# ADS1220RTD_BREWNO_V2.net
KiCad netlist of a schematic drawn in EAGLE
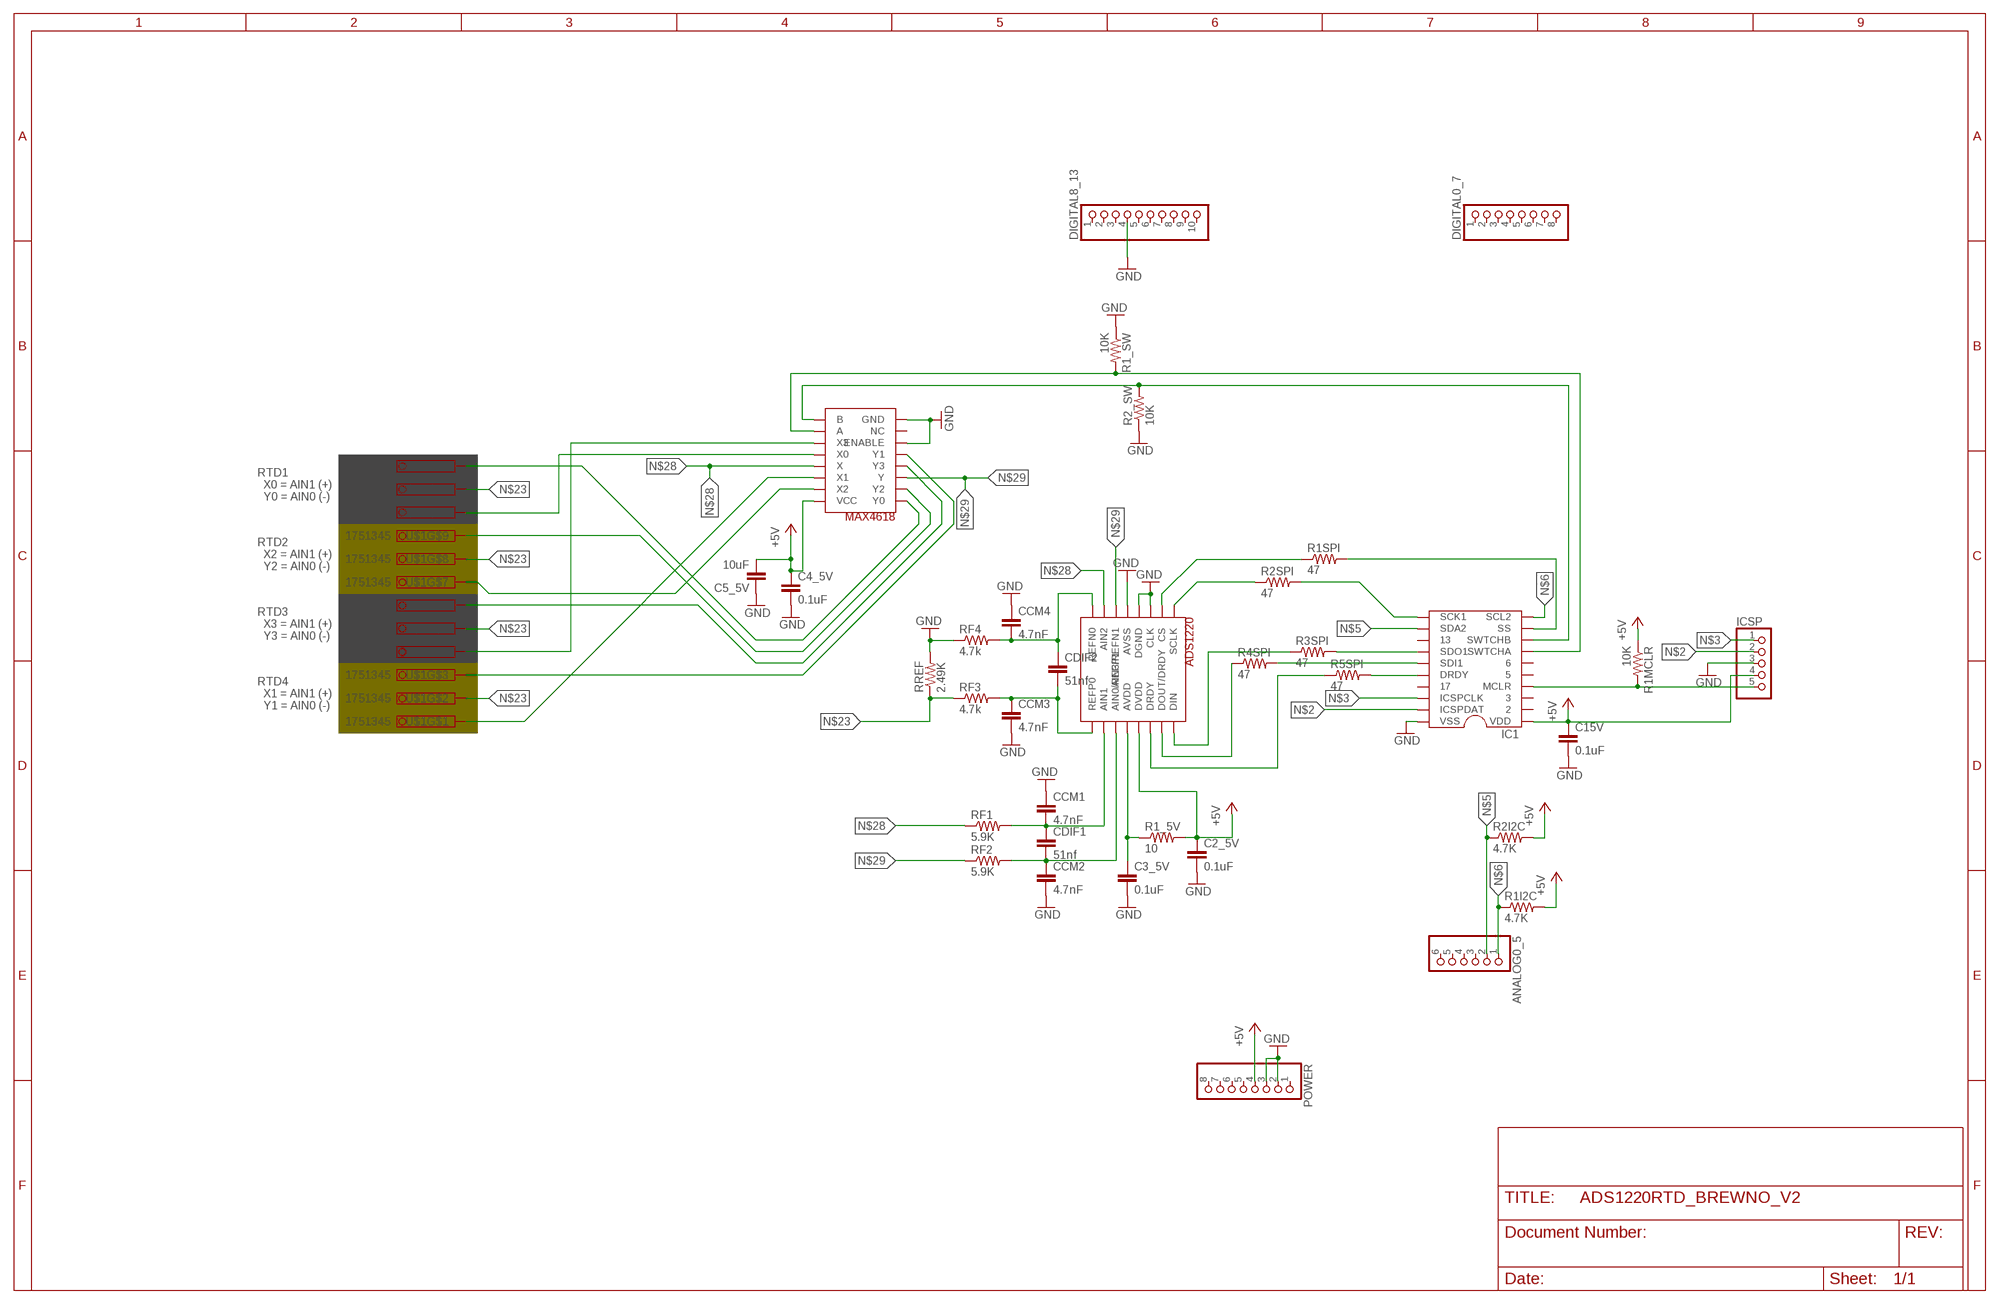
[diagram p0: schematic, sheet 1]

(export (version "E")
  (design (tool "Eeschema 10.0.6"))
  (components
    (comp (ref "ADS1220")
      (value "ADS1220")
      (footprint "eagle-import:TSSOP16")
      (libsource (lib "eagle-import") (part "ADS1220"))
    )
    (comp (ref "ANALOG0_5")
      (value "PINHD-1X6")
      (footprint "eagle-import:1X06")
      (libsource (lib "eagle-import") (part "PINHD-1X6"))
    )
    (comp (ref "C2_5V")
      (value "0.1uF")
      (footprint "eagle-import:C0603")
      (libsource (lib "eagle-import") (part "C-EUC0603"))
    )
    (comp (ref "C3_5V")
      (value "0.1uF")
      (footprint "eagle-import:C0603")
      (libsource (lib "eagle-import") (part "C-EUC0603"))
    )
    (comp (ref "C4_5V")
      (value "0.1uF")
      (footprint "eagle-import:C0603")
      (libsource (lib "eagle-import") (part "C-EUC0603"))
    )
    (comp (ref "C5_5V")
      (value "10uF")
      (footprint "eagle-import:C0603")
      (libsource (lib "eagle-import") (part "C-EUC0603"))
    )
    (comp (ref "C15V")
      (value "0.1uF")
      (footprint "eagle-import:C0603")
      (libsource (lib "eagle-import") (part "C-EUC0603"))
    )
    (comp (ref "CCM1")
      (value "4.7nF")
      (footprint "eagle-import:C0603")
      (libsource (lib "eagle-import") (part "C-EUC0603"))
    )
    (comp (ref "CCM2")
      (value "4.7nF")
      (footprint "eagle-import:C0603")
      (libsource (lib "eagle-import") (part "C-EUC0603"))
    )
    (comp (ref "CCM3")
      (value "4.7nF")
      (footprint "eagle-import:C0603")
      (libsource (lib "eagle-import") (part "C-EUC0603"))
    )
    (comp (ref "CCM4")
      (value "4.7nF")
      (footprint "eagle-import:C0603")
      (libsource (lib "eagle-import") (part "C-EUC0603"))
    )
    (comp (ref "CDIF1")
      (value "51nf")
      (footprint "eagle-import:C1206")
      (libsource (lib "eagle-import") (part "C-EUC1206"))
    )
    (comp (ref "CDIF2")
      (value "51nf")
      (footprint "eagle-import:C1206")
      (libsource (lib "eagle-import") (part "C-EUC1206"))
    )
    (comp (ref "DIGITAL0_7")
      (value "PINHD-1X8")
      (footprint "eagle-import:1X08")
      (libsource (lib "eagle-import") (part "PINHD-1X8"))
    )
    (comp (ref "DIGITAL8_13")
      (value "PINHD-1X10")
      (footprint "eagle-import:1X10")
      (libsource (lib "eagle-import") (part "PINHD-1X10"))
    )
    (comp (ref "IC1")
      (value "DIL20")
      (footprint "eagle-import:DIL20")
      (libsource (lib "eagle-import") (part "DIL20"))
    )
    (comp (ref "ICSP")
      (value "PINHD-1X5")
      (footprint "eagle-import:1X05")
      (libsource (lib "eagle-import") (part "PINHD-1X5"))
    )
    (comp (ref "MAX4618")
      (value "MAX4618CPE")
      (footprint "eagle-import:SO16")
      (libsource (lib "eagle-import") (part "MAX4618CPE"))
    )
    (comp (ref "POWER")
      (value "PINHD-1X8")
      (footprint "eagle-import:1X08")
      (libsource (lib "eagle-import") (part "PINHD-1X8"))
    )
    (comp (ref "R1I2C")
      (value "4.7K")
      (footprint "eagle-import:R0603")
      (libsource (lib "eagle-import") (part "R-US_R0603"))
    )
    (comp (ref "R1MCLR")
      (value "10K")
      (footprint "eagle-import:R0603")
      (libsource (lib "eagle-import") (part "R-US_R0603"))
    )
    (comp (ref "R1SPI")
      (value "47")
      (footprint "eagle-import:R0603")
      (libsource (lib "eagle-import") (part "R-US_R0603"))
    )
    (comp (ref "R1_5V")
      (value "10")
      (footprint "eagle-import:R0603")
      (libsource (lib "eagle-import") (part "R-US_R0603"))
    )
    (comp (ref "R1_SW")
      (value "10K")
      (footprint "eagle-import:R0603")
      (libsource (lib "eagle-import") (part "R-US_R0603"))
    )
    (comp (ref "R2I2C")
      (value "4.7K")
      (footprint "eagle-import:R0603")
      (libsource (lib "eagle-import") (part "R-US_R0603"))
    )
    (comp (ref "R2SPI")
      (value "47")
      (footprint "eagle-import:R0603")
      (libsource (lib "eagle-import") (part "R-US_R0603"))
    )
    (comp (ref "R2_SW")
      (value "10K")
      (footprint "eagle-import:R0603")
      (libsource (lib "eagle-import") (part "R-US_R0603"))
    )
    (comp (ref "R3SPI")
      (value "47")
      (footprint "eagle-import:R0603")
      (libsource (lib "eagle-import") (part "R-US_R0603"))
    )
    (comp (ref "R4SPI")
      (value "47")
      (footprint "eagle-import:R0603")
      (libsource (lib "eagle-import") (part "R-US_R0603"))
    )
    (comp (ref "R5SPI")
      (value "47")
      (footprint "eagle-import:R0603")
      (libsource (lib "eagle-import") (part "R-US_R0603"))
    )
    (comp (ref "RF1")
      (value "5.9K")
      (footprint "eagle-import:R0603")
      (libsource (lib "eagle-import") (part "R-US_R0603"))
    )
    (comp (ref "RF2")
      (value "5.9K")
      (footprint "eagle-import:R0603")
      (libsource (lib "eagle-import") (part "R-US_R0603"))
    )
    (comp (ref "RF3")
      (value "4.7k")
      (footprint "eagle-import:R0603")
      (libsource (lib "eagle-import") (part "R-US_R0603"))
    )
    (comp (ref "RF4")
      (value "4.7k")
      (footprint "eagle-import:R0603")
      (libsource (lib "eagle-import") (part "R-US_R0603"))
    )
    (comp (ref "RREF")
      (value "2.49K")
      (footprint "eagle-import:R0603")
      (libsource (lib "eagle-import") (part "R-US_R0603"))
    )
    (comp (ref "U$1")
      (value "1751345")
      (footprint "eagle-import:1751345")
      (libsource (lib "eagle-import") (part "1751345"))
    )
  )
  (nets
    (net (code "1") (name "+5V") (class "Default")
      (node (ref "ADS1220") (pin "13") (pinfunction "DVDD_13") (pintype "bidirectional"))
      (node (ref "C15V") (pin "1") (pinfunction "1_1") (pintype "passive"))
      (node (ref "C2_5V") (pin "1") (pinfunction "1_1") (pintype "passive"))
      (node (ref "C4_5V") (pin "1") (pinfunction "1_1") (pintype "passive"))
      (node (ref "C5_5V") (pin "2") (pinfunction "2_2") (pintype "passive"))
      (node (ref "IC1") (pin "1") (pinfunction "VDD_1") (pintype "passive"))
      (node (ref "ICSP") (pin "4") (pinfunction "4_4") (pintype "passive"))
      (node (ref "MAX4618") (pin "16") (pinfunction "VCC_16") (pintype "bidirectional"))
      (node (ref "POWER") (pin "4") (pinfunction "4_4") (pintype "passive"))
      (node (ref "R1I2C") (pin "2") (pinfunction "2_2") (pintype "passive"))
      (node (ref "R1MCLR") (pin "1") (pinfunction "1_1") (pintype "passive"))
      (node (ref "R1_5V") (pin "2") (pinfunction "2_2") (pintype "passive"))
      (node (ref "R2I2C") (pin "2") (pinfunction "2_2") (pintype "passive"))
    )
    (net (code "2") (name "GND") (class "Default")
      (node (ref "ADS1220") (pin "3") (pinfunction "CLK_3") (pintype "bidirectional"))
      (node (ref "ADS1220") (pin "4") (pinfunction "DGND_4") (pintype "bidirectional"))
      (node (ref "ADS1220") (pin "5") (pinfunction "AVSS_5") (pintype "bidirectional"))
      (node (ref "C15V") (pin "2") (pinfunction "2_2") (pintype "passive"))
      (node (ref "C2_5V") (pin "2") (pinfunction "2_2") (pintype "passive"))
      (node (ref "C3_5V") (pin "2") (pinfunction "2_2") (pintype "passive"))
      (node (ref "C4_5V") (pin "2") (pinfunction "2_2") (pintype "passive"))
      (node (ref "C5_5V") (pin "1") (pinfunction "1_1") (pintype "passive"))
      (node (ref "CCM1") (pin "1") (pinfunction "1_1") (pintype "passive"))
      (node (ref "CCM2") (pin "2") (pinfunction "2_2") (pintype "passive"))
      (node (ref "CCM3") (pin "2") (pinfunction "2_2") (pintype "passive"))
      (node (ref "CCM4") (pin "1") (pinfunction "1_1") (pintype "passive"))
      (node (ref "DIGITAL8_13") (pin "4") (pinfunction "4_4") (pintype "passive"))
      (node (ref "IC1") (pin "20") (pinfunction "VSS_20") (pintype "passive"))
      (node (ref "ICSP") (pin "3") (pinfunction "3_3") (pintype "passive"))
      (node (ref "MAX4618") (pin "6") (pinfunction "ENABLE_6") (pintype "bidirectional"))
      (node (ref "MAX4618") (pin "8") (pinfunction "GND_8") (pintype "bidirectional"))
      (node (ref "POWER") (pin "2") (pinfunction "2_2") (pintype "passive"))
      (node (ref "POWER") (pin "3") (pinfunction "3_3") (pintype "passive"))
      (node (ref "R1_SW") (pin "1") (pinfunction "1_1") (pintype "passive"))
      (node (ref "R2_SW") (pin "1") (pinfunction "1_1") (pintype "passive"))
      (node (ref "RF4") (pin "1") (pinfunction "1_1") (pintype "passive"))
      (node (ref "RREF") (pin "2") (pinfunction "2_2") (pintype "passive"))
    )
    (net (code "3") (name "N$2") (class "Default")
      (node (ref "IC1") (pin "19") (pinfunction "ICSPDAT_19") (pintype "passive"))
      (node (ref "ICSP") (pin "2") (pinfunction "2_2") (pintype "passive"))
    )
    (net (code "4") (name "N$3") (class "Default")
      (node (ref "IC1") (pin "18") (pinfunction "ICSPCLK_18") (pintype "passive"))
      (node (ref "ICSP") (pin "1") (pinfunction "1_1") (pintype "passive"))
    )
    (net (code "5") (name "N$5") (class "Default")
      (node (ref "ANALOG0_5") (pin "2") (pinfunction "2_2") (pintype "passive"))
      (node (ref "IC1") (pin "12") (pinfunction "SDA2_12") (pintype "passive"))
      (node (ref "R2I2C") (pin "1") (pinfunction "1_1") (pintype "passive"))
    )
    (net (code "6") (name "N$6") (class "Default")
      (node (ref "ANALOG0_5") (pin "1") (pinfunction "1_1") (pintype "passive"))
      (node (ref "IC1") (pin "10") (pinfunction "SCL2_10") (pintype "passive"))
      (node (ref "R1I2C") (pin "1") (pinfunction "1_1") (pintype "passive"))
    )
    (net (code "7") (name "N$23") (class "Default")
      (node (ref "RF3") (pin "1") (pinfunction "1_1") (pintype "passive"))
      (node (ref "RREF") (pin "1") (pinfunction "1_1") (pintype "passive"))
      (node (ref "U$1") (pin "11") (pinfunction "K_11") (pintype "passive"))
      (node (ref "U$1") (pin "2") (pinfunction "K_2") (pintype "passive"))
      (node (ref "U$1") (pin "5") (pinfunction "K_5") (pintype "passive"))
      (node (ref "U$1") (pin "8") (pinfunction "K_8") (pintype "passive"))
    )
    (net (code "8") (name "N$28") (class "Default")
      (node (ref "ADS1220") (pin "7") (pinfunction "AIN2_7") (pintype "bidirectional"))
      (node (ref "MAX4618") (pin "13") (pinfunction "X_13") (pintype "bidirectional"))
      (node (ref "RF1") (pin "1") (pinfunction "1_1") (pintype "passive"))
    )
    (net (code "9") (name "N$29") (class "Default")
      (node (ref "ADS1220") (pin "6") (pinfunction "AIN3/REFN1_6") (pintype "bidirectional"))
      (node (ref "MAX4618") (pin "3") (pinfunction "Y_3") (pintype "bidirectional"))
      (node (ref "RF2") (pin "1") (pinfunction "1_1") (pintype "passive"))
    )
    (net (code "10") (name "Net-(ADS1220-AIN0{slash}REFP1)") (class "Default")
      (node (ref "ADS1220") (pin "11") (pinfunction "AIN0/REFP1_11") (pintype "bidirectional"))
      (node (ref "CCM2") (pin "1") (pinfunction "1_1") (pintype "passive"))
      (node (ref "CDIF1") (pin "2") (pinfunction "2_2") (pintype "passive"))
      (node (ref "RF2") (pin "2") (pinfunction "2_2") (pintype "passive"))
    )
    (net (code "11") (name "Net-(ADS1220-AIN1)") (class "Default")
      (node (ref "ADS1220") (pin "10") (pinfunction "AIN1_10") (pintype "bidirectional"))
      (node (ref "CCM1") (pin "2") (pinfunction "2_2") (pintype "passive"))
      (node (ref "CDIF1") (pin "1") (pinfunction "1_1") (pintype "passive"))
      (node (ref "RF1") (pin "2") (pinfunction "2_2") (pintype "passive"))
    )
    (net (code "12") (name "Net-(ADS1220-AVDD)") (class "Default")
      (node (ref "ADS1220") (pin "12") (pinfunction "AVDD_12") (pintype "bidirectional"))
      (node (ref "C3_5V") (pin "1") (pinfunction "1_1") (pintype "passive"))
      (node (ref "R1_5V") (pin "1") (pinfunction "1_1") (pintype "passive"))
    )
    (net (code "13") (name "Net-(ADS1220-CS)") (class "Default")
      (node (ref "ADS1220") (pin "2") (pinfunction "CS_2") (pintype "bidirectional"))
      (node (ref "R1SPI") (pin "1") (pinfunction "1_1") (pintype "passive"))
    )
    (net (code "14") (name "Net-(ADS1220-DIN)") (class "Default")
      (node (ref "ADS1220") (pin "16") (pinfunction "DIN_16") (pintype "bidirectional"))
      (node (ref "R3SPI") (pin "1") (pinfunction "1_1") (pintype "passive"))
    )
    (net (code "15") (name "Net-(ADS1220-DOUT{slash}DRDY)") (class "Default")
      (node (ref "ADS1220") (pin "15") (pinfunction "DOUT/DRDY_15") (pintype "bidirectional"))
      (node (ref "R4SPI") (pin "1") (pinfunction "1_1") (pintype "passive"))
    )
    (net (code "16") (name "Net-(ADS1220-DRDY)") (class "Default")
      (node (ref "ADS1220") (pin "14") (pinfunction "DRDY_14") (pintype "bidirectional"))
      (node (ref "R5SPI") (pin "1") (pinfunction "1_1") (pintype "passive"))
    )
    (net (code "17") (name "Net-(ADS1220-REFN0)") (class "Default")
      (node (ref "ADS1220") (pin "8") (pinfunction "REFN0_8") (pintype "bidirectional"))
      (node (ref "CCM4") (pin "2") (pinfunction "2_2") (pintype "passive"))
      (node (ref "CDIF2") (pin "1") (pinfunction "1_1") (pintype "passive"))
      (node (ref "RF4") (pin "2") (pinfunction "2_2") (pintype "passive"))
    )
    (net (code "18") (name "Net-(ADS1220-REFP0)") (class "Default")
      (node (ref "ADS1220") (pin "9") (pinfunction "REFP0_9") (pintype "bidirectional"))
      (node (ref "CCM3") (pin "1") (pinfunction "1_1") (pintype "passive"))
      (node (ref "CDIF2") (pin "2") (pinfunction "2_2") (pintype "passive"))
      (node (ref "RF3") (pin "2") (pinfunction "2_2") (pintype "passive"))
    )
    (net (code "19") (name "Net-(ADS1220-SCLK)") (class "Default")
      (node (ref "ADS1220") (pin "1") (pinfunction "SCLK_1") (pintype "bidirectional"))
      (node (ref "R2SPI") (pin "1") (pinfunction "1_1") (pintype "passive"))
    )
    (net (code "20") (name "Net-(IC1-DRDY)") (class "Default")
      (node (ref "IC1") (pin "16") (pinfunction "DRDY_16") (pintype "passive"))
      (node (ref "R5SPI") (pin "2") (pinfunction "2_2") (pintype "passive"))
    )
    (net (code "21") (name "Net-(IC1-MCLR)") (class "Default")
      (node (ref "IC1") (pin "4") (pinfunction "MCLR_4") (pintype "passive"))
      (node (ref "ICSP") (pin "5") (pinfunction "5_5") (pintype "passive"))
      (node (ref "R1MCLR") (pin "2") (pinfunction "2_2") (pintype "passive"))
    )
    (net (code "22") (name "Net-(IC1-SCK1)") (class "Default")
      (node (ref "IC1") (pin "11") (pinfunction "SCK1_11") (pintype "passive"))
      (node (ref "R2SPI") (pin "2") (pinfunction "2_2") (pintype "passive"))
    )
    (net (code "23") (name "Net-(IC1-SDI1)") (class "Default")
      (node (ref "IC1") (pin "15") (pinfunction "SDI1_15") (pintype "passive"))
      (node (ref "R4SPI") (pin "2") (pinfunction "2_2") (pintype "passive"))
    )
    (net (code "24") (name "Net-(IC1-SDO1)") (class "Default")
      (node (ref "IC1") (pin "14") (pinfunction "SDO1_14") (pintype "passive"))
      (node (ref "R3SPI") (pin "2") (pinfunction "2_2") (pintype "passive"))
    )
    (net (code "25") (name "Net-(IC1-SS)") (class "Default")
      (node (ref "IC1") (pin "9") (pinfunction "SS_9") (pintype "passive"))
      (node (ref "R1SPI") (pin "2") (pinfunction "2_2") (pintype "passive"))
    )
    (net (code "26") (name "Net-(IC1-SWTCHA)") (class "Default")
      (node (ref "IC1") (pin "7") (pinfunction "SWTCHA_7") (pintype "passive"))
      (node (ref "MAX4618") (pin "10") (pinfunction "A_10") (pintype "bidirectional"))
      (node (ref "R1_SW") (pin "2") (pinfunction "2_2") (pintype "passive"))
    )
    (net (code "27") (name "Net-(IC1-SWTCHB)") (class "Default")
      (node (ref "IC1") (pin "8") (pinfunction "SWTCHB_8") (pintype "passive"))
      (node (ref "MAX4618") (pin "9") (pinfunction "B_9") (pintype "bidirectional"))
      (node (ref "R2_SW") (pin "2") (pinfunction "2_2") (pintype "passive"))
    )
    (net (code "28") (name "Net-(MAX4618-X0)") (class "Default")
      (node (ref "MAX4618") (pin "12") (pinfunction "X0_12") (pintype "bidirectional"))
      (node (ref "U$1") (pin "10") (pinfunction "K_10") (pintype "passive"))
    )
    (net (code "29") (name "Net-(MAX4618-X1)") (class "Default")
      (node (ref "MAX4618") (pin "14") (pinfunction "X1_14") (pintype "bidirectional"))
      (node (ref "U$1") (pin "1") (pinfunction "K_1") (pintype "passive"))
    )
    (net (code "30") (name "Net-(MAX4618-X2)") (class "Default")
      (node (ref "MAX4618") (pin "15") (pinfunction "X2_15") (pintype "bidirectional"))
      (node (ref "U$1") (pin "7") (pinfunction "K_7") (pintype "passive"))
    )
    (net (code "31") (name "Net-(MAX4618-X3)") (class "Default")
      (node (ref "MAX4618") (pin "11") (pinfunction "X3_11") (pintype "bidirectional"))
      (node (ref "U$1") (pin "4") (pinfunction "K_4") (pintype "passive"))
    )
    (net (code "32") (name "Net-(MAX4618-Y0)") (class "Default")
      (node (ref "MAX4618") (pin "1") (pinfunction "Y0_1") (pintype "bidirectional"))
      (node (ref "U$1") (pin "12") (pinfunction "K_12") (pintype "passive"))
    )
    (net (code "33") (name "Net-(MAX4618-Y1)") (class "Default")
      (node (ref "MAX4618") (pin "5") (pinfunction "Y1_5") (pintype "bidirectional"))
      (node (ref "U$1") (pin "3") (pinfunction "K_3") (pintype "passive"))
    )
    (net (code "34") (name "Net-(MAX4618-Y2)") (class "Default")
      (node (ref "MAX4618") (pin "2") (pinfunction "Y2_2") (pintype "bidirectional"))
      (node (ref "U$1") (pin "9") (pinfunction "K_9") (pintype "passive"))
    )
    (net (code "35") (name "Net-(MAX4618-Y3)") (class "Default")
      (node (ref "MAX4618") (pin "4") (pinfunction "Y3_4") (pintype "bidirectional"))
      (node (ref "U$1") (pin "6") (pinfunction "K_6") (pintype "passive"))
    )
    (net (code "36") (name "unconnected-(ANALOG0_5-Pad3)") (class "Default")
      (node (ref "ANALOG0_5") (pin "3") (pinfunction "3_3") (pintype "passive"))
    )
    (net (code "37") (name "unconnected-(ANALOG0_5-Pad4)") (class "Default")
      (node (ref "ANALOG0_5") (pin "4") (pinfunction "4_4") (pintype "passive"))
    )
    (net (code "38") (name "unconnected-(ANALOG0_5-Pad5)") (class "Default")
      (node (ref "ANALOG0_5") (pin "5") (pinfunction "5_5") (pintype "passive"))
    )
    (net (code "39") (name "unconnected-(ANALOG0_5-Pad6)") (class "Default")
      (node (ref "ANALOG0_5") (pin "6") (pinfunction "6_6") (pintype "passive"))
    )
    (net (code "40") (name "unconnected-(DIGITAL0_7-Pad1)") (class "Default")
      (node (ref "DIGITAL0_7") (pin "1") (pinfunction "1_1") (pintype "passive"))
    )
    (net (code "41") (name "unconnected-(DIGITAL0_7-Pad2)") (class "Default")
      (node (ref "DIGITAL0_7") (pin "2") (pinfunction "2_2") (pintype "passive"))
    )
    (net (code "42") (name "unconnected-(DIGITAL0_7-Pad3)") (class "Default")
      (node (ref "DIGITAL0_7") (pin "3") (pinfunction "3_3") (pintype "passive"))
    )
    (net (code "43") (name "unconnected-(DIGITAL0_7-Pad4)") (class "Default")
      (node (ref "DIGITAL0_7") (pin "4") (pinfunction "4_4") (pintype "passive"))
    )
    (net (code "44") (name "unconnected-(DIGITAL0_7-Pad5)") (class "Default")
      (node (ref "DIGITAL0_7") (pin "5") (pinfunction "5_5") (pintype "passive"))
    )
    (net (code "45") (name "unconnected-(DIGITAL0_7-Pad6)") (class "Default")
      (node (ref "DIGITAL0_7") (pin "6") (pinfunction "6_6") (pintype "passive"))
    )
    (net (code "46") (name "unconnected-(DIGITAL0_7-Pad7)") (class "Default")
      (node (ref "DIGITAL0_7") (pin "7") (pinfunction "7_7") (pintype "passive"))
    )
    (net (code "47") (name "unconnected-(DIGITAL0_7-Pad8)") (class "Default")
      (node (ref "DIGITAL0_7") (pin "8") (pinfunction "8_8") (pintype "passive"))
    )
    (net (code "48") (name "unconnected-(DIGITAL8_13-Pad1)") (class "Default")
      (node (ref "DIGITAL8_13") (pin "1") (pinfunction "1_1") (pintype "passive"))
    )
    (net (code "49") (name "unconnected-(DIGITAL8_13-Pad2)") (class "Default")
      (node (ref "DIGITAL8_13") (pin "2") (pinfunction "2_2") (pintype "passive"))
    )
    (net (code "50") (name "unconnected-(DIGITAL8_13-Pad3)") (class "Default")
      (node (ref "DIGITAL8_13") (pin "3") (pinfunction "3_3") (pintype "passive"))
    )
    (net (code "51") (name "unconnected-(DIGITAL8_13-Pad5)") (class "Default")
      (node (ref "DIGITAL8_13") (pin "5") (pinfunction "5_5") (pintype "passive"))
    )
    (net (code "52") (name "unconnected-(DIGITAL8_13-Pad6)") (class "Default")
      (node (ref "DIGITAL8_13") (pin "6") (pinfunction "6_6") (pintype "passive"))
    )
    (net (code "53") (name "unconnected-(DIGITAL8_13-Pad7)") (class "Default")
      (node (ref "DIGITAL8_13") (pin "7") (pinfunction "7_7") (pintype "passive"))
    )
    (net (code "54") (name "unconnected-(DIGITAL8_13-Pad8)") (class "Default")
      (node (ref "DIGITAL8_13") (pin "8") (pinfunction "8_8") (pintype "passive"))
    )
    (net (code "55") (name "unconnected-(DIGITAL8_13-Pad9)") (class "Default")
      (node (ref "DIGITAL8_13") (pin "9") (pinfunction "9_9") (pintype "passive"))
    )
    (net (code "56") (name "unconnected-(DIGITAL8_13-Pad10)") (class "Default")
      (node (ref "DIGITAL8_13") (pin "10") (pinfunction "10_10") (pintype "passive"))
    )
    (net (code "57") (name "unconnected-(IC1-Pad2)") (class "Default")
      (node (ref "IC1") (pin "2") (pinfunction "2_2") (pintype "passive"))
    )
    (net (code "58") (name "unconnected-(IC1-Pad3)") (class "Default")
      (node (ref "IC1") (pin "3") (pinfunction "3_3") (pintype "passive"))
    )
    (net (code "59") (name "unconnected-(IC1-Pad5)") (class "Default")
      (node (ref "IC1") (pin "5") (pinfunction "5_5") (pintype "passive"))
    )
    (net (code "60") (name "unconnected-(IC1-Pad6)") (class "Default")
      (node (ref "IC1") (pin "6") (pinfunction "6_6") (pintype "passive"))
    )
    (net (code "61") (name "unconnected-(IC1-Pad13)") (class "Default")
      (node (ref "IC1") (pin "13") (pinfunction "13_13") (pintype "passive"))
    )
    (net (code "62") (name "unconnected-(IC1-Pad17)") (class "Default")
      (node (ref "IC1") (pin "17") (pinfunction "17_17") (pintype "passive"))
    )
    (net (code "63") (name "unconnected-(MAX4618-NC-Pad7)") (class "Default")
      (node (ref "MAX4618") (pin "7") (pinfunction "NC_7") (pintype "bidirectional"))
    )
    (net (code "64") (name "unconnected-(POWER-Pad1)") (class "Default")
      (node (ref "POWER") (pin "1") (pinfunction "1_1") (pintype "passive"))
    )
    (net (code "65") (name "unconnected-(POWER-Pad5)") (class "Default")
      (node (ref "POWER") (pin "5") (pinfunction "5_5") (pintype "passive"))
    )
    (net (code "66") (name "unconnected-(POWER-Pad6)") (class "Default")
      (node (ref "POWER") (pin "6") (pinfunction "6_6") (pintype "passive"))
    )
    (net (code "67") (name "unconnected-(POWER-Pad7)") (class "Default")
      (node (ref "POWER") (pin "7") (pinfunction "7_7") (pintype "passive"))
    )
    (net (code "68") (name "unconnected-(POWER-Pad8)") (class "Default")
      (node (ref "POWER") (pin "8") (pinfunction "8_8") (pintype "passive"))
    )
  )
)
